# ADC_Scaling.net
KiCad netlist of a schematic drawn in EAGLE
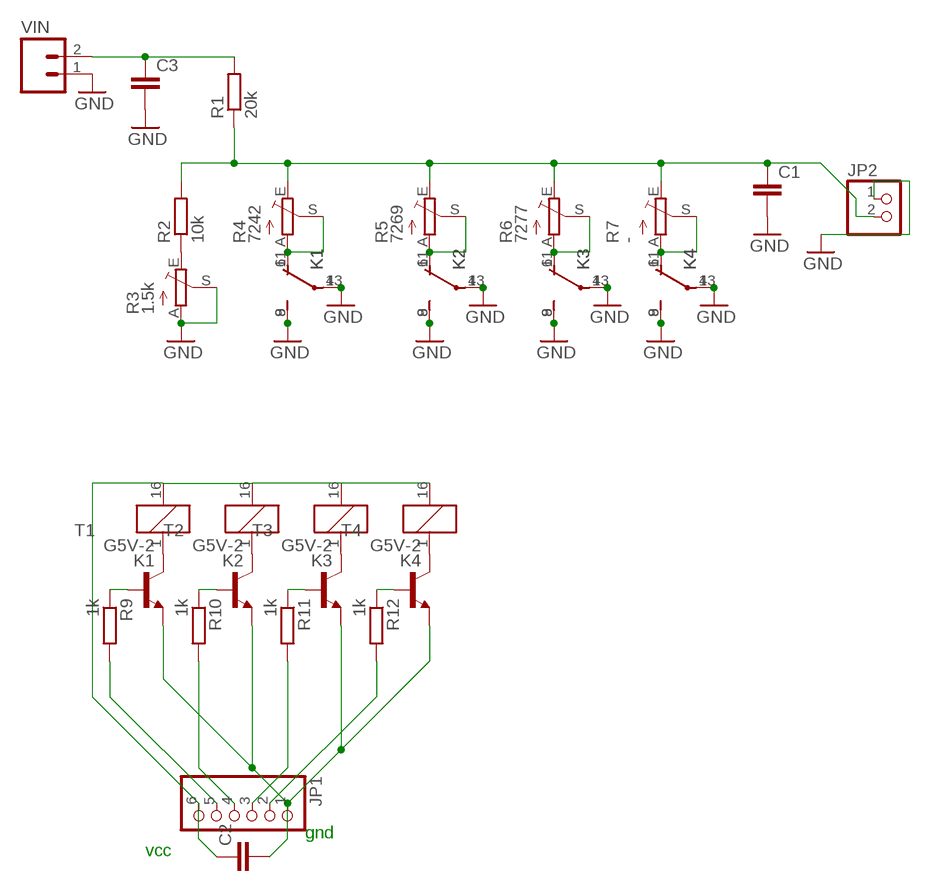
[diagram p0: schematic, sheet 1]

(export (version "E")
  (design (tool "Eeschema 10.0.6"))
  (components
    (comp (ref "C1")
      (value "C-EUC0805")
      (footprint "eagle-import:C0805")
      (libsource (lib "eagle-import") (part "C-EUC0805"))
    )
    (comp (ref "C2")
      (value "C-EUC0805")
      (footprint "eagle-import:C0805")
      (libsource (lib "eagle-import") (part "C-EUC0805"))
    )
    (comp (ref "C3")
      (value "C-EUC0805")
      (footprint "eagle-import:C0805")
      (libsource (lib "eagle-import") (part "C-EUC0805"))
    )
    (comp (ref "JP1")
      (value "PINHD-1X6")
      (footprint "eagle-import:1X06")
      (libsource (lib "eagle-import") (part "PINHD-1X6"))
    )
    (comp (ref "JP2")
      (value "PINHD-1X2")
      (footprint "eagle-import:1X02")
      (libsource (lib "eagle-import") (part "PINHD-1X2"))
    )
    (comp (ref "K1")
      (value "G5V-2")
      (footprint "eagle-import:G5V-2")
      (fields (field (name "MPN") "G5V-2 5DC"))
      (libsource (lib "eagle-import") (part "G5V-2"))
    )
    (comp (ref "K2")
      (value "G5V-2")
      (footprint "eagle-import:G5V-2")
      (fields (field (name "MPN") "G5V-2 5DC"))
      (libsource (lib "eagle-import") (part "G5V-2"))
    )
    (comp (ref "K3")
      (value "G5V-2")
      (footprint "eagle-import:G5V-2")
      (fields (field (name "MPN") "G5V-2 5DC"))
      (libsource (lib "eagle-import") (part "G5V-2"))
    )
    (comp (ref "K4")
      (value "G5V-2")
      (footprint "eagle-import:G5V-2")
      (fields (field (name "MPN") "G5V-2 5DC"))
      (libsource (lib "eagle-import") (part "G5V-2"))
    )
    (comp (ref "R1")
      (value "20k")
      (footprint "eagle-import:M0805")
      (libsource (lib "eagle-import") (part "R-EU_M0805"))
    )
    (comp (ref "R2")
      (value "10k")
      (footprint "eagle-import:M0805")
      (libsource (lib "eagle-import") (part "R-EU_M0805"))
    )
    (comp (ref "R3")
      (value "1.5k")
      (footprint "eagle-import:RJ9W")
      (libsource (lib "eagle-import") (part "TRIM_EU-RJ9W"))
    )
    (comp (ref "R4")
      (value "7242")
      (footprint "eagle-import:RJ9W")
      (libsource (lib "eagle-import") (part "TRIM_EU-RJ9W"))
    )
    (comp (ref "R5")
      (value "7269")
      (footprint "eagle-import:RJ9W")
      (libsource (lib "eagle-import") (part "TRIM_EU-RJ9W"))
    )
    (comp (ref "R6")
      (value "7277")
      (footprint "eagle-import:RJ9W")
      (libsource (lib "eagle-import") (part "TRIM_EU-RJ9W"))
    )
    (comp (ref "R7")
      (value "-")
      (footprint "eagle-import:RJ9W")
      (libsource (lib "eagle-import") (part "TRIM_EU-RJ9W"))
    )
    (comp (ref "R9")
      (value "1k")
      (footprint "eagle-import:M0805")
      (libsource (lib "eagle-import") (part "R-EU_M0805"))
    )
    (comp (ref "R10")
      (value "1k")
      (footprint "eagle-import:M0805")
      (libsource (lib "eagle-import") (part "R-EU_M0805"))
    )
    (comp (ref "R11")
      (value "1k")
      (footprint "eagle-import:M0805")
      (libsource (lib "eagle-import") (part "R-EU_M0805"))
    )
    (comp (ref "R12")
      (value "1k")
      (footprint "eagle-import:M0805")
      (libsource (lib "eagle-import") (part "R-EU_M0805"))
    )
    (comp (ref "T1")
      (value "MMBTA42LT1-NPN-SOT23-BEC")
      (footprint "eagle-import:SOT23-BEC")
      (libsource (lib "eagle-import") (part "-NPN-SOT23-BECMMBTA42LT1"))
    )
    (comp (ref "T2")
      (value "MMBTA42LT1-NPN-SOT23-BEC")
      (footprint "eagle-import:SOT23-BEC")
      (libsource (lib "eagle-import") (part "-NPN-SOT23-BECMMBTA42LT1"))
    )
    (comp (ref "T3")
      (value "MMBTA42LT1-NPN-SOT23-BEC")
      (footprint "eagle-import:SOT23-BEC")
      (libsource (lib "eagle-import") (part "-NPN-SOT23-BECMMBTA42LT1"))
    )
    (comp (ref "T4")
      (value "MMBTA42LT1-NPN-SOT23-BEC")
      (footprint "eagle-import:SOT23-BEC")
      (libsource (lib "eagle-import") (part "-NPN-SOT23-BECMMBTA42LT1"))
    )
    (comp (ref "VIN")
      (value "M02POLAR")
      (footprint "eagle-import:MOLEX-1X2")
      (libsource (lib "eagle-import") (part "M02POLAR"))
    )
  )
  (nets
    (net (code "1") (name "GND") (class "Default")
      (node (ref "C1") (pin "2") (pinfunction "2_2") (pintype "passive"))
      (node (ref "C3") (pin "2") (pinfunction "2_2") (pintype "passive"))
      (node (ref "JP2") (pin "1") (pinfunction "1_1") (pintype "passive"))
      (node (ref "K1") (pin "13") (pinfunction "P_13") (pintype "passive"))
      (node (ref "K1") (pin "4") (pinfunction "P_4") (pintype "passive"))
      (node (ref "K1") (pin "8") (pinfunction "S_8") (pintype "passive"))
      (node (ref "K1") (pin "9") (pinfunction "S_9") (pintype "passive"))
      (node (ref "K2") (pin "13") (pinfunction "P_13") (pintype "passive"))
      (node (ref "K2") (pin "4") (pinfunction "P_4") (pintype "passive"))
      (node (ref "K2") (pin "8") (pinfunction "S_8") (pintype "passive"))
      (node (ref "K2") (pin "9") (pinfunction "S_9") (pintype "passive"))
      (node (ref "K3") (pin "13") (pinfunction "P_13") (pintype "passive"))
      (node (ref "K3") (pin "4") (pinfunction "P_4") (pintype "passive"))
      (node (ref "K3") (pin "8") (pinfunction "S_8") (pintype "passive"))
      (node (ref "K3") (pin "9") (pinfunction "S_9") (pintype "passive"))
      (node (ref "K4") (pin "13") (pinfunction "P_13") (pintype "passive"))
      (node (ref "K4") (pin "4") (pinfunction "P_4") (pintype "passive"))
      (node (ref "K4") (pin "8") (pinfunction "S_8") (pintype "passive"))
      (node (ref "K4") (pin "9") (pinfunction "S_9") (pintype "passive"))
      (node (ref "R3") (pin "A") (pinfunction "A_A") (pintype "passive"))
      (node (ref "R3") (pin "S") (pinfunction "S_S") (pintype "passive"))
      (node (ref "VIN") (pin "1") (pinfunction "1_1") (pintype "passive"))
    )
    (net (code "2") (name "Net-(C1-Pad1)") (class "Default")
      (node (ref "C1") (pin "1") (pinfunction "1_1") (pintype "passive"))
      (node (ref "JP2") (pin "2") (pinfunction "2_2") (pintype "passive"))
      (node (ref "R1") (pin "1") (pinfunction "1_1") (pintype "passive"))
      (node (ref "R2") (pin "2") (pinfunction "2_2") (pintype "passive"))
      (node (ref "R4") (pin "E") (pinfunction "E_E") (pintype "passive"))
      (node (ref "R5") (pin "E") (pinfunction "E_E") (pintype "passive"))
      (node (ref "R6") (pin "E") (pinfunction "E_E") (pintype "passive"))
      (node (ref "R7") (pin "E") (pinfunction "E_E") (pintype "passive"))
    )
    (net (code "3") (name "Net-(C2-Pad2)") (class "Default")
      (node (ref "C2") (pin "2") (pinfunction "2_2") (pintype "passive"))
      (node (ref "JP1") (pin "1") (pinfunction "1_1") (pintype "passive"))
      (node (ref "T1") (pin "E") (pinfunction "E_E") (pintype "passive"))
      (node (ref "T2") (pin "E") (pinfunction "E_E") (pintype "passive"))
      (node (ref "T3") (pin "E") (pinfunction "E_E") (pintype "passive"))
      (node (ref "T4") (pin "E") (pinfunction "E_E") (pintype "passive"))
    )
    (net (code "4") (name "Net-(C3-Pad1)") (class "Default")
      (node (ref "C3") (pin "1") (pinfunction "1_1") (pintype "passive"))
      (node (ref "R1") (pin "2") (pinfunction "2_2") (pintype "passive"))
      (node (ref "VIN") (pin "2") (pinfunction "2_2") (pintype "passive"))
    )
    (net (code "5") (name "Net-(JP1-Pad2)") (class "Default")
      (node (ref "JP1") (pin "2") (pinfunction "2_2") (pintype "passive"))
      (node (ref "R12") (pin "2") (pinfunction "2_2") (pintype "passive"))
    )
    (net (code "6") (name "Net-(JP1-Pad3)") (class "Default")
      (node (ref "JP1") (pin "3") (pinfunction "3_3") (pintype "passive"))
      (node (ref "R11") (pin "2") (pinfunction "2_2") (pintype "passive"))
    )
    (net (code "7") (name "Net-(JP1-Pad4)") (class "Default")
      (node (ref "JP1") (pin "4") (pinfunction "4_4") (pintype "passive"))
      (node (ref "R10") (pin "2") (pinfunction "2_2") (pintype "passive"))
    )
    (net (code "8") (name "Net-(JP1-Pad5)") (class "Default")
      (node (ref "JP1") (pin "5") (pinfunction "5_5") (pintype "passive"))
      (node (ref "R9") (pin "2") (pinfunction "2_2") (pintype "passive"))
    )
    (net (code "9") (name "Net-(K1-Pad1)") (class "Default")
      (node (ref "K1") (pin "1") (pinfunction "1_1") (pintype "passive"))
      (node (ref "T1") (pin "C") (pinfunction "C_C") (pintype "passive"))
    )
    (net (code "10") (name "Net-(K1A-O)") (class "Default")
      (node (ref "K1") (pin "11") (pinfunction "O_11") (pintype "passive"))
      (node (ref "K1") (pin "6") (pinfunction "O_6") (pintype "passive"))
      (node (ref "R4") (pin "A") (pinfunction "A_A") (pintype "passive"))
      (node (ref "R4") (pin "S") (pinfunction "S_S") (pintype "passive"))
    )
    (net (code "11") (name "Net-(K1C-2)") (class "Default")
      (node (ref "C2") (pin "1") (pinfunction "1_1") (pintype "passive"))
      (node (ref "JP1") (pin "6") (pinfunction "6_6") (pintype "passive"))
      (node (ref "K1") (pin "16") (pinfunction "2_16") (pintype "passive"))
      (node (ref "K2") (pin "16") (pinfunction "2_16") (pintype "passive"))
      (node (ref "K3") (pin "16") (pinfunction "2_16") (pintype "passive"))
      (node (ref "K4") (pin "16") (pinfunction "2_16") (pintype "passive"))
    )
    (net (code "12") (name "Net-(K2-Pad1)") (class "Default")
      (node (ref "K2") (pin "1") (pinfunction "1_1") (pintype "passive"))
      (node (ref "T2") (pin "C") (pinfunction "C_C") (pintype "passive"))
    )
    (net (code "13") (name "Net-(K2A-O)") (class "Default")
      (node (ref "K2") (pin "11") (pinfunction "O_11") (pintype "passive"))
      (node (ref "K2") (pin "6") (pinfunction "O_6") (pintype "passive"))
      (node (ref "R5") (pin "A") (pinfunction "A_A") (pintype "passive"))
      (node (ref "R5") (pin "S") (pinfunction "S_S") (pintype "passive"))
    )
    (net (code "14") (name "Net-(K3-Pad1)") (class "Default")
      (node (ref "K3") (pin "1") (pinfunction "1_1") (pintype "passive"))
      (node (ref "T3") (pin "C") (pinfunction "C_C") (pintype "passive"))
    )
    (net (code "15") (name "Net-(K3A-O)") (class "Default")
      (node (ref "K3") (pin "11") (pinfunction "O_11") (pintype "passive"))
      (node (ref "K3") (pin "6") (pinfunction "O_6") (pintype "passive"))
      (node (ref "R6") (pin "A") (pinfunction "A_A") (pintype "passive"))
      (node (ref "R6") (pin "S") (pinfunction "S_S") (pintype "passive"))
    )
    (net (code "16") (name "Net-(K4-Pad1)") (class "Default")
      (node (ref "K4") (pin "1") (pinfunction "1_1") (pintype "passive"))
      (node (ref "T4") (pin "C") (pinfunction "C_C") (pintype "passive"))
    )
    (net (code "17") (name "Net-(K4A-O)") (class "Default")
      (node (ref "K4") (pin "11") (pinfunction "O_11") (pintype "passive"))
      (node (ref "K4") (pin "6") (pinfunction "O_6") (pintype "passive"))
      (node (ref "R7") (pin "A") (pinfunction "A_A") (pintype "passive"))
      (node (ref "R7") (pin "S") (pinfunction "S_S") (pintype "passive"))
    )
    (net (code "18") (name "Net-(R2-Pad1)") (class "Default")
      (node (ref "R2") (pin "1") (pinfunction "1_1") (pintype "passive"))
      (node (ref "R3") (pin "E") (pinfunction "E_E") (pintype "passive"))
    )
    (net (code "19") (name "Net-(R9-Pad1)") (class "Default")
      (node (ref "R9") (pin "1") (pinfunction "1_1") (pintype "passive"))
      (node (ref "T1") (pin "B") (pinfunction "B_B") (pintype "passive"))
    )
    (net (code "20") (name "Net-(R10-Pad1)") (class "Default")
      (node (ref "R10") (pin "1") (pinfunction "1_1") (pintype "passive"))
      (node (ref "T2") (pin "B") (pinfunction "B_B") (pintype "passive"))
    )
    (net (code "21") (name "Net-(R11-Pad1)") (class "Default")
      (node (ref "R11") (pin "1") (pinfunction "1_1") (pintype "passive"))
      (node (ref "T3") (pin "B") (pinfunction "B_B") (pintype "passive"))
    )
    (net (code "22") (name "Net-(R12-Pad1)") (class "Default")
      (node (ref "R12") (pin "1") (pinfunction "1_1") (pintype "passive"))
      (node (ref "T4") (pin "B") (pinfunction "B_B") (pintype "passive"))
    )
  )
)
